# DA_uno_shield_3_0.net
KiCad netlist of a schematic drawn in EAGLE
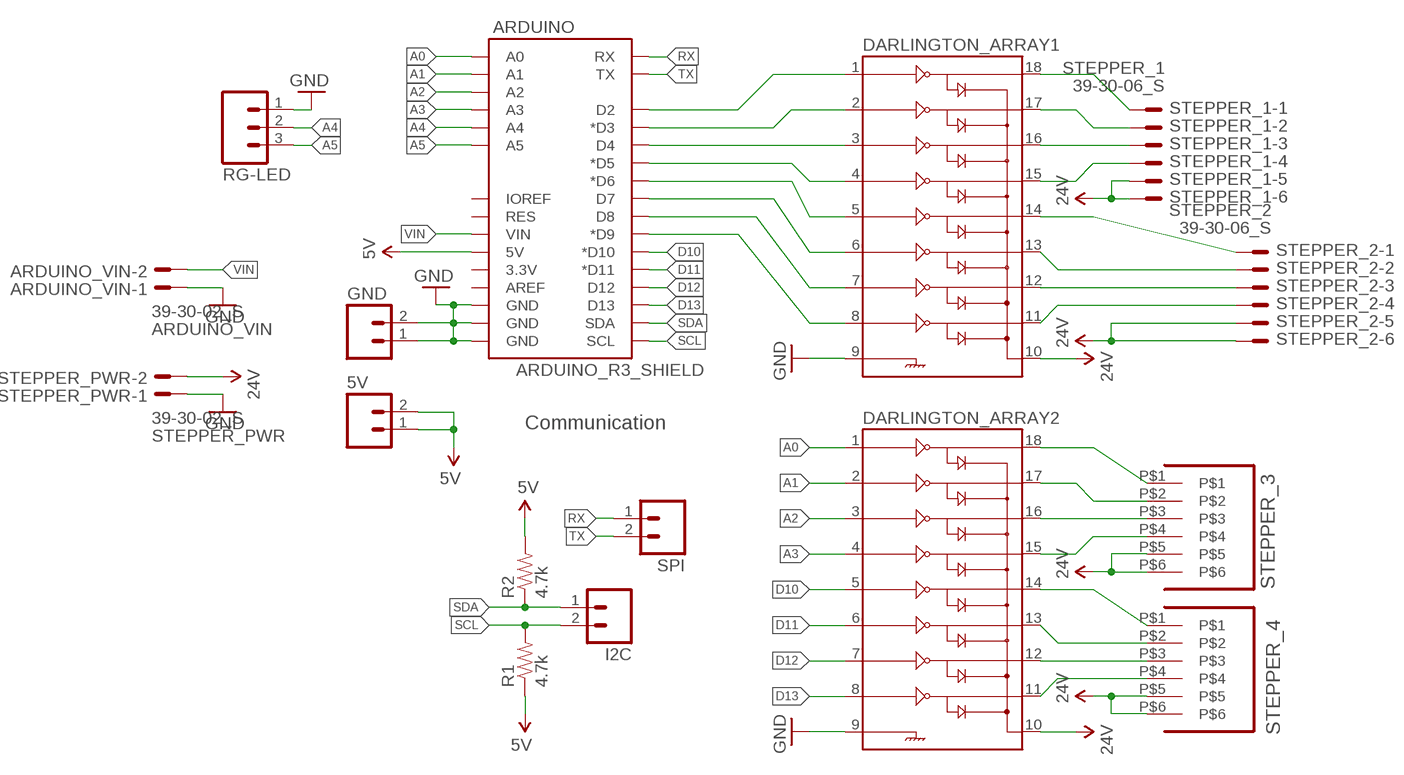
[diagram p0: schematic, sheet 1]

(export (version "E")
  (design (tool "Eeschema 10.0.6"))
  (components
    (comp (ref "5V")
      (value "M021X02_NO_SILK")
      (footprint "eagle-import:1X02_NO_SILK")
      (libsource (lib "eagle-import") (part "M021X02_NO_SILK"))
    )
    (comp (ref "ARDUINO")
      (value "ARDUINO_R3_SHIELD")
      (footprint "eagle-import:UNO_R3_SHIELD")
      (libsource (lib "eagle-import") (part "ARDUINO_R3_SHIELD"))
    )
    (comp (ref "ARDUINO_VIN")
      (value "39-30-02_S")
      (footprint "eagle-import:39-30-_02_")
      (libsource (lib "eagle-import") (part "39-30-?02?_S"))
    )
    (comp (ref "DARLINGTON_ARRAY1")
      (value "ULN2803DIP")
      (footprint "eagle-import:DIL18")
      (libsource (lib "eagle-import") (part "ULN2803DIP"))
    )
    (comp (ref "DARLINGTON_ARRAY2")
      (value "ULN2803DIP")
      (footprint "eagle-import:DIL18")
      (libsource (lib "eagle-import") (part "ULN2803DIP"))
    )
    (comp (ref "GND")
      (value "M021X02_NO_SILK")
      (footprint "eagle-import:1X02_NO_SILK")
      (libsource (lib "eagle-import") (part "M021X02_NO_SILK"))
    )
    (comp (ref "I2C")
      (value "M021X02_NO_SILK")
      (footprint "eagle-import:1X02_NO_SILK")
      (libsource (lib "eagle-import") (part "M021X02_NO_SILK"))
    )
    (comp (ref "R1")
      (value "4.7k")
      (footprint "eagle-import:AXIAL-0.3-KIT")
      (libsource (lib "eagle-import") (part "RESISTORKIT"))
    )
    (comp (ref "R2")
      (value "4.7k")
      (footprint "eagle-import:AXIAL-0.3-KIT")
      (libsource (lib "eagle-import") (part "RESISTORKIT"))
    )
    (comp (ref "RG-LED")
      (value "M03LOCK_NO_SILK")
      (footprint "eagle-import:1X03_LOCK_NO_SILK")
      (libsource (lib "eagle-import") (part "M03LOCK_NO_SILK"))
    )
    (comp (ref "SPI")
      (value "M021X02_NO_SILK")
      (footprint "eagle-import:1X02_NO_SILK")
      (libsource (lib "eagle-import") (part "M021X02_NO_SILK"))
    )
    (comp (ref "STEPPER_1")
      (value "39-30-06_S")
      (footprint "eagle-import:39-30-_06_")
      (libsource (lib "eagle-import") (part "39-30-?06?_S"))
    )
    (comp (ref "STEPPER_2")
      (value "39-30-06_S")
      (footprint "eagle-import:39-30-_06_")
      (libsource (lib "eagle-import") (part "39-30-?06?_S"))
    )
    (comp (ref "STEPPER_3")
      (value "39-29-06")
      (footprint "eagle-import:39-29-_06_")
      (libsource (lib "eagle-import") (part "39-29-?06?"))
    )
    (comp (ref "STEPPER_4")
      (value "39-29-06")
      (footprint "eagle-import:39-29-_06_")
      (libsource (lib "eagle-import") (part "39-29-?06?"))
    )
    (comp (ref "STEPPER_PWR")
      (value "39-30-02_S")
      (footprint "eagle-import:39-30-_02_")
      (libsource (lib "eagle-import") (part "39-30-?02?_S"))
    )
  )
  (nets
    (net (code "1") (name "5V") (class "Default")
      (node (ref "5V") (pin "1") (pinfunction "1_1") (pintype "passive"))
      (node (ref "5V") (pin "2") (pinfunction "2_2") (pintype "passive"))
      (node (ref "ARDUINO") (pin "5V") (pinfunction "5V_5V") (pintype "bidirectional"))
      (node (ref "R1") (pin "P$1") (pinfunction "1_P$1") (pintype "passive"))
      (node (ref "R2") (pin "P$2") (pinfunction "2_P$2") (pintype "passive"))
    )
    (net (code "2") (name "24V") (class "Default")
      (node (ref "DARLINGTON_ARRAY1") (pin "10") (pinfunction "10_10") (pintype "bidirectional"))
      (node (ref "DARLINGTON_ARRAY2") (pin "10") (pinfunction "10_10") (pintype "bidirectional"))
      (node (ref "STEPPER_1") (pin "5") (pinfunction "P_5") (pintype "passive"))
      (node (ref "STEPPER_1") (pin "6") (pinfunction "P_6") (pintype "passive"))
      (node (ref "STEPPER_2") (pin "5") (pinfunction "P_5") (pintype "passive"))
      (node (ref "STEPPER_2") (pin "6") (pinfunction "P_6") (pintype "passive"))
      (node (ref "STEPPER_3") (pin "P$5") (pinfunction "P$5_P$5") (pintype "bidirectional"))
      (node (ref "STEPPER_3") (pin "P$6") (pinfunction "P$6_P$6") (pintype "bidirectional"))
      (node (ref "STEPPER_4") (pin "P$5") (pinfunction "P$5_P$5") (pintype "bidirectional"))
      (node (ref "STEPPER_4") (pin "P$6") (pinfunction "P$6_P$6") (pintype "bidirectional"))
      (node (ref "STEPPER_PWR") (pin "2") (pinfunction "P_2") (pintype "passive"))
    )
    (net (code "3") (name "A0") (class "Default")
      (node (ref "ARDUINO") (pin "A0") (pinfunction "A0_A0") (pintype "bidirectional"))
      (node (ref "DARLINGTON_ARRAY2") (pin "1") (pinfunction "1_1") (pintype "bidirectional"))
    )
    (net (code "4") (name "A1") (class "Default")
      (node (ref "ARDUINO") (pin "A1") (pinfunction "A1_A1") (pintype "bidirectional"))
      (node (ref "DARLINGTON_ARRAY2") (pin "2") (pinfunction "2_2") (pintype "bidirectional"))
    )
    (net (code "5") (name "A2") (class "Default")
      (node (ref "ARDUINO") (pin "A2") (pinfunction "A2_A2") (pintype "bidirectional"))
      (node (ref "DARLINGTON_ARRAY2") (pin "3") (pinfunction "3_3") (pintype "bidirectional"))
    )
    (net (code "6") (name "A3") (class "Default")
      (node (ref "ARDUINO") (pin "A3") (pinfunction "A3_A3") (pintype "bidirectional"))
      (node (ref "DARLINGTON_ARRAY2") (pin "4") (pinfunction "4_4") (pintype "bidirectional"))
    )
    (net (code "7") (name "A4") (class "Default")
      (node (ref "ARDUINO") (pin "A4") (pinfunction "A4_A4") (pintype "bidirectional"))
      (node (ref "RG-LED") (pin "2") (pinfunction "2_2") (pintype "passive"))
    )
    (net (code "8") (name "A5") (class "Default")
      (node (ref "ARDUINO") (pin "A5") (pinfunction "A5_A5") (pintype "bidirectional"))
      (node (ref "RG-LED") (pin "3") (pinfunction "3_3") (pintype "passive"))
    )
    (net (code "9") (name "D10") (class "Default")
      (node (ref "ARDUINO") (pin "D10") (pinfunction "*D10_D10") (pintype "bidirectional"))
      (node (ref "DARLINGTON_ARRAY2") (pin "5") (pinfunction "5_5") (pintype "bidirectional"))
    )
    (net (code "10") (name "D11") (class "Default")
      (node (ref "ARDUINO") (pin "D11") (pinfunction "*D11_D11") (pintype "bidirectional"))
      (node (ref "DARLINGTON_ARRAY2") (pin "6") (pinfunction "6_6") (pintype "bidirectional"))
    )
    (net (code "11") (name "D12") (class "Default")
      (node (ref "ARDUINO") (pin "D12") (pinfunction "D12_D12") (pintype "bidirectional"))
      (node (ref "DARLINGTON_ARRAY2") (pin "7") (pinfunction "7_7") (pintype "bidirectional"))
    )
    (net (code "12") (name "D13") (class "Default")
      (node (ref "ARDUINO") (pin "D13") (pinfunction "D13_D13") (pintype "bidirectional"))
      (node (ref "DARLINGTON_ARRAY2") (pin "8") (pinfunction "8_8") (pintype "bidirectional"))
    )
    (net (code "13") (name "GND") (class "Default")
      (node (ref "ARDUINO") (pin "GND@0") (pinfunction "GND_GND@0") (pintype "bidirectional"))
      (node (ref "ARDUINO") (pin "GND@1") (pinfunction "GND_GND@1") (pintype "bidirectional"))
      (node (ref "ARDUINO") (pin "GND@2") (pinfunction "GND_GND@2") (pintype "bidirectional"))
      (node (ref "ARDUINO_VIN") (pin "1") (pinfunction "P_1") (pintype "passive"))
      (node (ref "DARLINGTON_ARRAY1") (pin "9") (pinfunction "9_9") (pintype "bidirectional"))
      (node (ref "DARLINGTON_ARRAY2") (pin "9") (pinfunction "9_9") (pintype "bidirectional"))
      (node (ref "GND") (pin "1") (pinfunction "1_1") (pintype "passive"))
      (node (ref "GND") (pin "2") (pinfunction "2_2") (pintype "passive"))
      (node (ref "RG-LED") (pin "1") (pinfunction "1_1") (pintype "passive"))
      (node (ref "STEPPER_PWR") (pin "1") (pinfunction "P_1") (pintype "passive"))
    )
    (net (code "14") (name "Net-(ARDUINO-*D3)") (class "Default")
      (node (ref "ARDUINO") (pin "D3") (pinfunction "*D3_D3") (pintype "bidirectional"))
      (node (ref "DARLINGTON_ARRAY1") (pin "2") (pinfunction "2_2") (pintype "bidirectional"))
    )
    (net (code "15") (name "Net-(ARDUINO-*D5)") (class "Default")
      (node (ref "ARDUINO") (pin "D5") (pinfunction "*D5_D5") (pintype "bidirectional"))
      (node (ref "DARLINGTON_ARRAY1") (pin "4") (pinfunction "4_4") (pintype "bidirectional"))
    )
    (net (code "16") (name "Net-(ARDUINO-*D6)") (class "Default")
      (node (ref "ARDUINO") (pin "D6") (pinfunction "*D6_D6") (pintype "bidirectional"))
      (node (ref "DARLINGTON_ARRAY1") (pin "5") (pinfunction "5_5") (pintype "bidirectional"))
    )
    (net (code "17") (name "Net-(ARDUINO-*D9)") (class "Default")
      (node (ref "ARDUINO") (pin "D9") (pinfunction "*D9_D9") (pintype "bidirectional"))
      (node (ref "DARLINGTON_ARRAY1") (pin "8") (pinfunction "8_8") (pintype "bidirectional"))
    )
    (net (code "18") (name "Net-(ARDUINO-PadD2)") (class "Default")
      (node (ref "ARDUINO") (pin "D2") (pinfunction "D2_D2") (pintype "bidirectional"))
      (node (ref "DARLINGTON_ARRAY1") (pin "1") (pinfunction "1_1") (pintype "bidirectional"))
    )
    (net (code "19") (name "Net-(ARDUINO-PadD4)") (class "Default")
      (node (ref "ARDUINO") (pin "D4") (pinfunction "D4_D4") (pintype "bidirectional"))
      (node (ref "DARLINGTON_ARRAY1") (pin "3") (pinfunction "3_3") (pintype "bidirectional"))
    )
    (net (code "20") (name "Net-(ARDUINO-PadD7)") (class "Default")
      (node (ref "ARDUINO") (pin "D7") (pinfunction "D7_D7") (pintype "bidirectional"))
      (node (ref "DARLINGTON_ARRAY1") (pin "6") (pinfunction "6_6") (pintype "bidirectional"))
    )
    (net (code "21") (name "Net-(ARDUINO-PadD8)") (class "Default")
      (node (ref "ARDUINO") (pin "D8") (pinfunction "D8_D8") (pintype "bidirectional"))
      (node (ref "DARLINGTON_ARRAY1") (pin "7") (pinfunction "7_7") (pintype "bidirectional"))
    )
    (net (code "22") (name "Net-(DARLINGTON_ARRAY2-Pad11)") (class "Default")
      (node (ref "DARLINGTON_ARRAY2") (pin "11") (pinfunction "11_11") (pintype "bidirectional"))
      (node (ref "STEPPER_4") (pin "P$4") (pinfunction "P$4_P$4") (pintype "bidirectional"))
    )
    (net (code "23") (name "Net-(DARLINGTON_ARRAY2-Pad12)") (class "Default")
      (node (ref "DARLINGTON_ARRAY2") (pin "12") (pinfunction "12_12") (pintype "bidirectional"))
      (node (ref "STEPPER_4") (pin "P$3") (pinfunction "P$3_P$3") (pintype "bidirectional"))
    )
    (net (code "24") (name "Net-(DARLINGTON_ARRAY2-Pad13)") (class "Default")
      (node (ref "DARLINGTON_ARRAY2") (pin "13") (pinfunction "13_13") (pintype "bidirectional"))
      (node (ref "STEPPER_4") (pin "P$2") (pinfunction "P$2_P$2") (pintype "bidirectional"))
    )
    (net (code "25") (name "Net-(DARLINGTON_ARRAY2-Pad14)") (class "Default")
      (node (ref "DARLINGTON_ARRAY2") (pin "14") (pinfunction "14_14") (pintype "bidirectional"))
      (node (ref "STEPPER_4") (pin "P$1") (pinfunction "P$1_P$1") (pintype "bidirectional"))
    )
    (net (code "26") (name "Net-(DARLINGTON_ARRAY2-Pad15)") (class "Default")
      (node (ref "DARLINGTON_ARRAY2") (pin "15") (pinfunction "15_15") (pintype "bidirectional"))
      (node (ref "STEPPER_3") (pin "P$4") (pinfunction "P$4_P$4") (pintype "bidirectional"))
    )
    (net (code "27") (name "Net-(DARLINGTON_ARRAY2-Pad16)") (class "Default")
      (node (ref "DARLINGTON_ARRAY2") (pin "16") (pinfunction "16_16") (pintype "bidirectional"))
      (node (ref "STEPPER_3") (pin "P$3") (pinfunction "P$3_P$3") (pintype "bidirectional"))
    )
    (net (code "28") (name "Net-(DARLINGTON_ARRAY2-Pad17)") (class "Default")
      (node (ref "DARLINGTON_ARRAY2") (pin "17") (pinfunction "17_17") (pintype "bidirectional"))
      (node (ref "STEPPER_3") (pin "P$2") (pinfunction "P$2_P$2") (pintype "bidirectional"))
    )
    (net (code "29") (name "Net-(DARLINGTON_ARRAY2-Pad18)") (class "Default")
      (node (ref "DARLINGTON_ARRAY2") (pin "18") (pinfunction "18_18") (pintype "bidirectional"))
      (node (ref "STEPPER_3") (pin "P$1") (pinfunction "P$1_P$1") (pintype "bidirectional"))
    )
    (net (code "30") (name "Net-(STEPPER_1A-P)") (class "Default")
      (node (ref "DARLINGTON_ARRAY1") (pin "18") (pinfunction "18_18") (pintype "bidirectional"))
      (node (ref "STEPPER_1") (pin "1") (pinfunction "P_1") (pintype "passive"))
    )
    (net (code "31") (name "Net-(STEPPER_1B-P)") (class "Default")
      (node (ref "DARLINGTON_ARRAY1") (pin "17") (pinfunction "17_17") (pintype "bidirectional"))
      (node (ref "STEPPER_1") (pin "2") (pinfunction "P_2") (pintype "passive"))
    )
    (net (code "32") (name "Net-(STEPPER_1C-P)") (class "Default")
      (node (ref "DARLINGTON_ARRAY1") (pin "16") (pinfunction "16_16") (pintype "bidirectional"))
      (node (ref "STEPPER_1") (pin "3") (pinfunction "P_3") (pintype "passive"))
    )
    (net (code "33") (name "Net-(STEPPER_1D-P)") (class "Default")
      (node (ref "DARLINGTON_ARRAY1") (pin "15") (pinfunction "15_15") (pintype "bidirectional"))
      (node (ref "STEPPER_1") (pin "4") (pinfunction "P_4") (pintype "passive"))
    )
    (net (code "34") (name "Net-(STEPPER_2A-P)") (class "Default")
      (node (ref "DARLINGTON_ARRAY1") (pin "14") (pinfunction "14_14") (pintype "bidirectional"))
      (node (ref "STEPPER_2") (pin "1") (pinfunction "P_1") (pintype "passive"))
    )
    (net (code "35") (name "Net-(STEPPER_2B-P)") (class "Default")
      (node (ref "DARLINGTON_ARRAY1") (pin "13") (pinfunction "13_13") (pintype "bidirectional"))
      (node (ref "STEPPER_2") (pin "2") (pinfunction "P_2") (pintype "passive"))
    )
    (net (code "36") (name "Net-(STEPPER_2C-P)") (class "Default")
      (node (ref "DARLINGTON_ARRAY1") (pin "12") (pinfunction "12_12") (pintype "bidirectional"))
      (node (ref "STEPPER_2") (pin "3") (pinfunction "P_3") (pintype "passive"))
    )
    (net (code "37") (name "Net-(STEPPER_2D-P)") (class "Default")
      (node (ref "DARLINGTON_ARRAY1") (pin "11") (pinfunction "11_11") (pintype "bidirectional"))
      (node (ref "STEPPER_2") (pin "4") (pinfunction "P_4") (pintype "passive"))
    )
    (net (code "38") (name "RX") (class "Default")
      (node (ref "ARDUINO") (pin "RX") (pinfunction "RX_RX") (pintype "bidirectional"))
      (node (ref "SPI") (pin "1") (pinfunction "1_1") (pintype "passive"))
    )
    (net (code "39") (name "SCL") (class "Default")
      (node (ref "ARDUINO") (pin "SCL") (pinfunction "SCL_SCL") (pintype "bidirectional"))
      (node (ref "I2C") (pin "2") (pinfunction "2_2") (pintype "passive"))
      (node (ref "R1") (pin "P$2") (pinfunction "2_P$2") (pintype "passive"))
    )
    (net (code "40") (name "SDA") (class "Default")
      (node (ref "ARDUINO") (pin "SDA") (pinfunction "SDA_SDA") (pintype "bidirectional"))
      (node (ref "I2C") (pin "1") (pinfunction "1_1") (pintype "passive"))
      (node (ref "R2") (pin "P$1") (pinfunction "1_P$1") (pintype "passive"))
    )
    (net (code "41") (name "TX") (class "Default")
      (node (ref "ARDUINO") (pin "TX") (pinfunction "TX_TX") (pintype "bidirectional"))
      (node (ref "SPI") (pin "2") (pinfunction "2_2") (pintype "passive"))
    )
    (net (code "42") (name "VIN") (class "Default")
      (node (ref "ARDUINO") (pin "VIN") (pinfunction "VIN_VIN") (pintype "bidirectional"))
      (node (ref "ARDUINO_VIN") (pin "2") (pinfunction "P_2") (pintype "passive"))
    )
    (net (code "43") (name "unconnected-(ARDUINO-Pad3.3V)") (class "Default")
      (node (ref "ARDUINO") (pin "3.3V") (pinfunction "3.3V_3.3V") (pintype "bidirectional"))
    )
    (net (code "44") (name "unconnected-(ARDUINO-PadAREF)") (class "Default")
      (node (ref "ARDUINO") (pin "AREF") (pinfunction "AREF_AREF") (pintype "bidirectional"))
    )
    (net (code "45") (name "unconnected-(ARDUINO-PadIOREF)") (class "Default")
      (node (ref "ARDUINO") (pin "IOREF") (pinfunction "IOREF_IOREF") (pintype "bidirectional"))
    )
    (net (code "46") (name "unconnected-(ARDUINO-PadRES)") (class "Default")
      (node (ref "ARDUINO") (pin "RES") (pinfunction "RES_RES") (pintype "bidirectional"))
    )
  )
)
